# bat_mini6.net
KiCad netlist of a schematic drawn in EAGLE
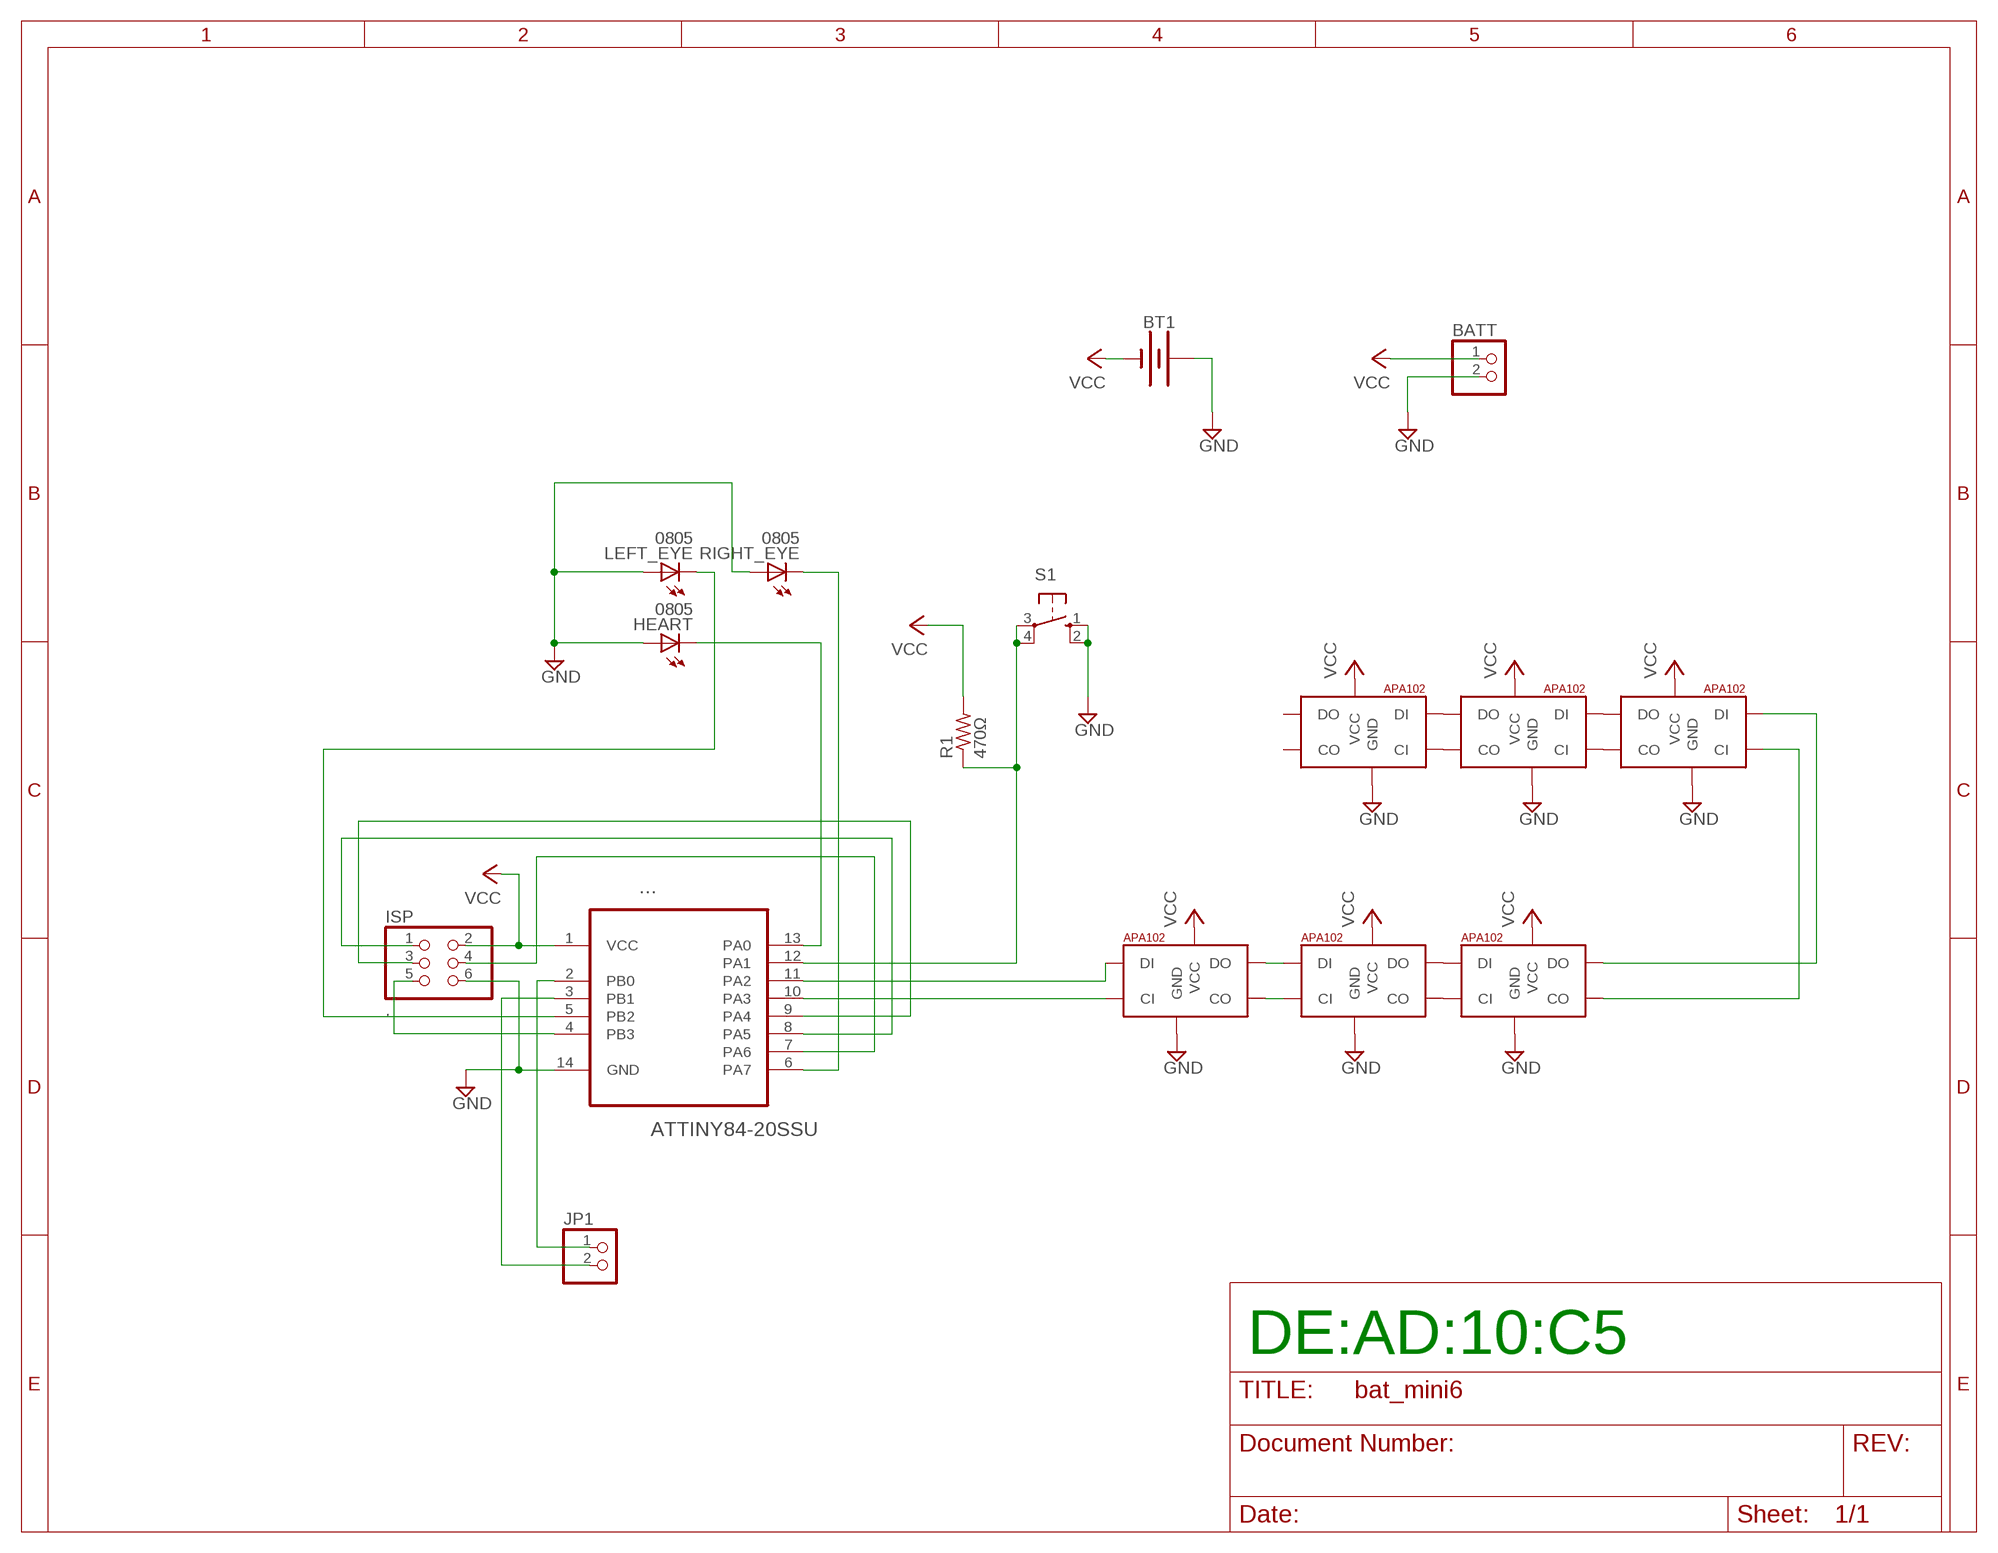
[diagram p0: schematic, sheet 1]

(export (version "E")
  (design (tool "Eeschema 10.0.6"))
  (components
    (comp (ref "...")
      (value "ATTINY84-20SSU")
      (footprint "eagle-import:SOIC127P600X175-14N")
      (libsource (lib "eagle-import") (part "ATTINY84-20SSU"))
    )
    (comp (ref "BATT")
      (value "PINHD-1X2")
      (footprint "eagle-import:1X02")
      (libsource (lib "eagle-import") (part "PINHD-1X2"))
    )
    (comp (ref "BT1")
      (value "BATTERY-20MM_SMD_4LEGS")
      (footprint "eagle-import:BATTCON_20MM_4LEGS")
      (libsource (lib "eagle-import") (part "BATTERY-20MM_SMD_4LEGS"))
    )
    (comp (ref "HEART")
      (value "0805")
      (footprint "eagle-import:CHIP-LED0805")
      (libsource (lib "eagle-import") (part "LEDCHIP-LED0805"))
    )
    (comp (ref "ISP")
      (value ".")
      (footprint "eagle-import:2X03")
      (libsource (lib "eagle-import") (part "PINHD-2X3"))
    )
    (comp (ref "JP1")
      (value "PINHD-1X2")
      (footprint "eagle-import:1X02")
      (libsource (lib "eagle-import") (part "PINHD-1X2"))
    )
    (comp (ref "LEFT_EYE")
      (value "0805")
      (footprint "eagle-import:CHIP-LED0805")
      (libsource (lib "eagle-import") (part "LEDCHIP-LED0805"))
    )
    (comp (ref "R1")
      (value "470Ω")
      (footprint "eagle-import:R0805")
      (libsource (lib "eagle-import") (part "R-US_R0805"))
    )
    (comp (ref "RIGHT_EYE")
      (value "0805")
      (footprint "eagle-import:CHIP-LED0805")
      (libsource (lib "eagle-import") (part "LEDCHIP-LED0805"))
    )
    (comp (ref "S1")
      (value "10-XX")
      (footprint "eagle-import:B3F-10XX")
      (fields (field (name "MPN") "B3F-1000"))
      (libsource (lib "eagle-import") (part "10-XX"))
    )
    (comp (ref "U$1")
      (value "APA1025050")
      (footprint "eagle-import:APA102_5050")
      (libsource (lib "eagle-import") (part "APA1025050"))
    )
    (comp (ref "U$2")
      (value "APA1025050")
      (footprint "eagle-import:APA102_5050")
      (libsource (lib "eagle-import") (part "APA1025050"))
    )
    (comp (ref "U$3")
      (value "APA1025050")
      (footprint "eagle-import:APA102_5050")
      (libsource (lib "eagle-import") (part "APA1025050"))
    )
    (comp (ref "U$5")
      (value "APA1025050")
      (footprint "eagle-import:APA102_5050")
      (libsource (lib "eagle-import") (part "APA1025050"))
    )
    (comp (ref "U$6")
      (value "APA1025050")
      (footprint "eagle-import:APA102_5050")
      (libsource (lib "eagle-import") (part "APA1025050"))
    )
    (comp (ref "U$7")
      (value "APA1025050")
      (footprint "eagle-import:APA102_5050")
      (libsource (lib "eagle-import") (part "APA1025050"))
    )
  )
  (nets
    (net (code "1") (name "GND") (class "Default")
      (node (ref "...") (pin "14") (pinfunction "GND_14") (pintype "passive"))
      (node (ref "BATT") (pin "2") (pinfunction "2_2") (pintype "passive"))
      (node (ref "BT1") (pin "POSITIVE@1") (pinfunction "+_POSITIVE@1") (pintype "power_in"))
      (node (ref "BT1") (pin "POSITIVE@2") (pinfunction "+_POSITIVE@2") (pintype "power_in"))
      (node (ref "BT1") (pin "POSITIVE@3") (pinfunction "+_POSITIVE@3") (pintype "power_in"))
      (node (ref "BT1") (pin "POSITIVE@4") (pinfunction "+_POSITIVE@4") (pintype "power_in"))
      (node (ref "HEART") (pin "A") (pinfunction "A_A") (pintype "passive"))
      (node (ref "ISP") (pin "6") (pinfunction "6_6") (pintype "passive"))
      (node (ref "LEFT_EYE") (pin "A") (pinfunction "A_A") (pintype "passive"))
      (node (ref "RIGHT_EYE") (pin "A") (pinfunction "A_A") (pintype "passive"))
      (node (ref "S1") (pin "1") (pinfunction "S_1") (pintype "passive"))
      (node (ref "S1") (pin "2") (pinfunction "S1_2") (pintype "passive"))
      (node (ref "U$1") (pin "6") (pinfunction "GND_6") (pintype "bidirectional"))
      (node (ref "U$2") (pin "6") (pinfunction "GND_6") (pintype "bidirectional"))
      (node (ref "U$3") (pin "6") (pinfunction "GND_6") (pintype "bidirectional"))
      (node (ref "U$5") (pin "6") (pinfunction "GND_6") (pintype "bidirectional"))
      (node (ref "U$6") (pin "6") (pinfunction "GND_6") (pintype "bidirectional"))
      (node (ref "U$7") (pin "6") (pinfunction "GND_6") (pintype "bidirectional"))
    )
    (net (code "2") (name "Net-(...-PA0)") (class "Default")
      (node (ref "...") (pin "13") (pinfunction "PA0_13") (pintype "bidirectional"))
      (node (ref "HEART") (pin "C") (pinfunction "C_C") (pintype "passive"))
    )
    (net (code "3") (name "Net-(...-PA1)") (class "Default")
      (node (ref "...") (pin "12") (pinfunction "PA1_12") (pintype "bidirectional"))
      (node (ref "R1") (pin "1") (pinfunction "1_1") (pintype "passive"))
      (node (ref "S1") (pin "3") (pinfunction "P_3") (pintype "passive"))
      (node (ref "S1") (pin "4") (pinfunction "P1_4") (pintype "passive"))
    )
    (net (code "4") (name "Net-(...-PA2)") (class "Default")
      (node (ref "...") (pin "11") (pinfunction "PA2_11") (pintype "bidirectional"))
      (node (ref "U$1") (pin "4") (pinfunction "DI_4") (pintype "bidirectional"))
    )
    (net (code "5") (name "Net-(...-PA3)") (class "Default")
      (node (ref "...") (pin "10") (pinfunction "PA3_10") (pintype "bidirectional"))
      (node (ref "U$1") (pin "5") (pinfunction "CI_5") (pintype "bidirectional"))
    )
    (net (code "6") (name "Net-(...-PA4)") (class "Default")
      (node (ref "...") (pin "9") (pinfunction "PA4_9") (pintype "bidirectional"))
      (node (ref "ISP") (pin "3") (pinfunction "3_3") (pintype "passive"))
    )
    (net (code "7") (name "Net-(...-PA5)") (class "Default")
      (node (ref "...") (pin "8") (pinfunction "PA5_8") (pintype "bidirectional"))
      (node (ref "ISP") (pin "1") (pinfunction "1_1") (pintype "passive"))
    )
    (net (code "8") (name "Net-(...-PA6)") (class "Default")
      (node (ref "...") (pin "7") (pinfunction "PA6_7") (pintype "bidirectional"))
      (node (ref "ISP") (pin "4") (pinfunction "4_4") (pintype "passive"))
    )
    (net (code "9") (name "Net-(...-PA7)") (class "Default")
      (node (ref "...") (pin "6") (pinfunction "PA7_6") (pintype "bidirectional"))
      (node (ref "RIGHT_EYE") (pin "C") (pinfunction "C_C") (pintype "passive"))
    )
    (net (code "10") (name "Net-(...-PB0)") (class "Default")
      (node (ref "...") (pin "2") (pinfunction "PB0_2") (pintype "bidirectional"))
      (node (ref "JP1") (pin "1") (pinfunction "1_1") (pintype "passive"))
    )
    (net (code "11") (name "Net-(...-PB1)") (class "Default")
      (node (ref "...") (pin "3") (pinfunction "PB1_3") (pintype "bidirectional"))
      (node (ref "JP1") (pin "2") (pinfunction "2_2") (pintype "passive"))
    )
    (net (code "12") (name "Net-(...-PB2)") (class "Default")
      (node (ref "...") (pin "5") (pinfunction "PB2_5") (pintype "bidirectional"))
      (node (ref "LEFT_EYE") (pin "C") (pinfunction "C_C") (pintype "passive"))
    )
    (net (code "13") (name "Net-(...-PB3)") (class "Default")
      (node (ref "...") (pin "4") (pinfunction "PB3_4") (pintype "bidirectional"))
      (node (ref "ISP") (pin "5") (pinfunction "5_5") (pintype "passive"))
    )
    (net (code "14") (name "Net-(U$1-CO)") (class "Default")
      (node (ref "U$1") (pin "2") (pinfunction "CO_2") (pintype "bidirectional"))
      (node (ref "U$2") (pin "5") (pinfunction "CI_5") (pintype "bidirectional"))
    )
    (net (code "15") (name "Net-(U$1-DO)") (class "Default")
      (node (ref "U$1") (pin "3") (pinfunction "DO_3") (pintype "bidirectional"))
      (node (ref "U$2") (pin "4") (pinfunction "DI_4") (pintype "bidirectional"))
    )
    (net (code "16") (name "Net-(U$2-CO)") (class "Default")
      (node (ref "U$2") (pin "2") (pinfunction "CO_2") (pintype "bidirectional"))
      (node (ref "U$3") (pin "5") (pinfunction "CI_5") (pintype "bidirectional"))
    )
    (net (code "17") (name "Net-(U$2-DO)") (class "Default")
      (node (ref "U$2") (pin "3") (pinfunction "DO_3") (pintype "bidirectional"))
      (node (ref "U$3") (pin "4") (pinfunction "DI_4") (pintype "bidirectional"))
    )
    (net (code "18") (name "Net-(U$3-CO)") (class "Default")
      (node (ref "U$3") (pin "2") (pinfunction "CO_2") (pintype "bidirectional"))
      (node (ref "U$5") (pin "5") (pinfunction "CI_5") (pintype "bidirectional"))
    )
    (net (code "19") (name "Net-(U$3-DO)") (class "Default")
      (node (ref "U$3") (pin "3") (pinfunction "DO_3") (pintype "bidirectional"))
      (node (ref "U$5") (pin "4") (pinfunction "DI_4") (pintype "bidirectional"))
    )
    (net (code "20") (name "Net-(U$5-CO)") (class "Default")
      (node (ref "U$5") (pin "2") (pinfunction "CO_2") (pintype "bidirectional"))
      (node (ref "U$6") (pin "5") (pinfunction "CI_5") (pintype "bidirectional"))
    )
    (net (code "21") (name "Net-(U$5-DO)") (class "Default")
      (node (ref "U$5") (pin "3") (pinfunction "DO_3") (pintype "bidirectional"))
      (node (ref "U$6") (pin "4") (pinfunction "DI_4") (pintype "bidirectional"))
    )
    (net (code "22") (name "Net-(U$6-CO)") (class "Default")
      (node (ref "U$6") (pin "2") (pinfunction "CO_2") (pintype "bidirectional"))
      (node (ref "U$7") (pin "5") (pinfunction "CI_5") (pintype "bidirectional"))
    )
    (net (code "23") (name "Net-(U$6-DO)") (class "Default")
      (node (ref "U$6") (pin "3") (pinfunction "DO_3") (pintype "bidirectional"))
      (node (ref "U$7") (pin "4") (pinfunction "DI_4") (pintype "bidirectional"))
    )
    (net (code "24") (name "VCC") (class "Default")
      (node (ref "...") (pin "1") (pinfunction "VCC_1") (pintype "power_in"))
      (node (ref "BATT") (pin "1") (pinfunction "1_1") (pintype "passive"))
      (node (ref "BT1") (pin "NEGATIVE") (pinfunction "-_NEGATIVE") (pintype "power_in"))
      (node (ref "ISP") (pin "2") (pinfunction "2_2") (pintype "passive"))
      (node (ref "R1") (pin "2") (pinfunction "2_2") (pintype "passive"))
      (node (ref "U$1") (pin "1") (pinfunction "VCC_1") (pintype "bidirectional"))
      (node (ref "U$2") (pin "1") (pinfunction "VCC_1") (pintype "bidirectional"))
      (node (ref "U$3") (pin "1") (pinfunction "VCC_1") (pintype "bidirectional"))
      (node (ref "U$5") (pin "1") (pinfunction "VCC_1") (pintype "bidirectional"))
      (node (ref "U$6") (pin "1") (pinfunction "VCC_1") (pintype "bidirectional"))
      (node (ref "U$7") (pin "1") (pinfunction "VCC_1") (pintype "bidirectional"))
    )
    (net (code "25") (name "unconnected-(U$7-CO-Pad2)") (class "Default")
      (node (ref "U$7") (pin "2") (pinfunction "CO_2") (pintype "bidirectional"))
    )
    (net (code "26") (name "unconnected-(U$7-DO-Pad3)") (class "Default")
      (node (ref "U$7") (pin "3") (pinfunction "DO_3") (pintype "bidirectional"))
    )
  )
)
